# LC_Filter.net
KiCad netlist of a schematic drawn in Altium Designer
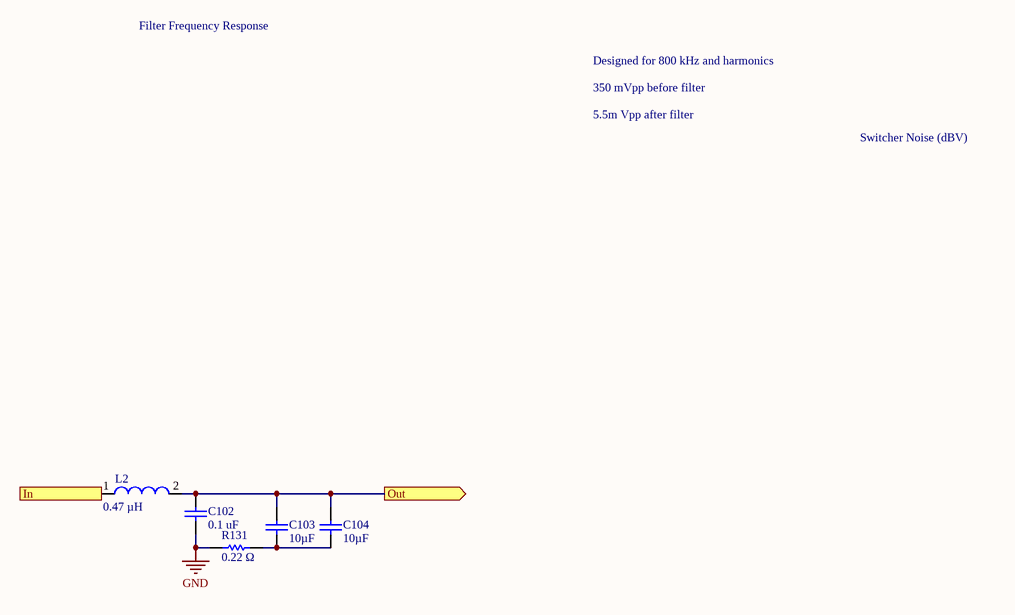
[diagram p0: LC_Filter.SchDoc]

(export (version "E")
  (design (tool "Eeschema 10.0.6"))
  (components
    (comp (ref "C102")
      (value "0.1 uF")
      (footprint "CAPC0402(1005)60_L")
      (description "CAP 100nF 16V ±5% 0402 (1005 Metric) Thickness 0.6mm SMD")
      (fields (field (name "TOLERANCE") "Â±5%"))
      (libsource (lib "Altium Content Vault") (part "CAP"))
    )
    (comp (ref "C103")
      (value "EMK107BBJ106MA-T")
      (footprint "CAPC1608X100X35LL20T25")
      (description "Chip Capacitor, 10 uF, +/- 20%, 16 V, -55 to 85 degC, 0603 (1608 Metric), RoHS, Tape and Reel")
      (fields
        (field (name "CAPACITANCE") "10µF")
        (field (name "MANUFACTURER") "Taiyo Yuden")
        (field (name "TOLERANCE") "±20%")
      )
      (libsource (lib "Altium Content Vault") (part "CAP-NP-2"))
    )
    (comp (ref "C104")
      (value "EMK107BBJ106MA-T")
      (footprint "CAPC1608X100X35LL20T25")
      (description "Chip Capacitor, 10 uF, +/- 20%, 16 V, -55 to 85 degC, 0603 (1608 Metric), RoHS, Tape and Reel")
      (fields
        (field (name "CAPACITANCE") "10µF")
        (field (name "MANUFACTURER") "Taiyo Yuden")
        (field (name "TOLERANCE") "±20%")
      )
      (libsource (lib "Altium Content Vault") (part "CAP-NP-2"))
    )
    (comp (ref "L2")
      (value "74404300047")
      (footprint "WE-TPC-4828-MH")
      (description "SMD Shielded Tiny Power Inductor WE-TPC, L = 0.47 µH")
      (fields (field (name "INDUCTANCE") "0.47 µH"))
      (libsource (lib "Altium Content Vault") (part "PAS-IND-INDUCTOR-2"))
    )
    (comp (ref "R131")
      (value "0.22 Ω")
      (footprint "RESC1608X55X30NL15T15")
      (fields (field (name "PART NUMBER") "ERJ-3RQFR22V") (field (name "MANUFACTURER") "Panasonic"))
      (libsource (lib "Altium Content Vault") (part "RES"))
    )
  )
  (nets
    (net (code "1") (name "/In") (class "Default")
      (node (ref "L2") (pin "1") (pinfunction "1_1") (pintype "passive"))
    )
    (net (code "2") (name "/Out") (class "Default")
      (node (ref "C102") (pin "2") (pinfunction "2_2") (pintype "passive"))
      (node (ref "C103") (pin "2") (pinfunction "2_2") (pintype "passive"))
      (node (ref "C104") (pin "2") (pinfunction "2_2") (pintype "passive"))
      (node (ref "L2") (pin "2") (pinfunction "2_2") (pintype "passive"))
    )
    (net (code "3") (name "GND") (class "Default")
      (node (ref "C102") (pin "1") (pinfunction "1_1") (pintype "passive"))
      (node (ref "R131") (pin "1") (pinfunction "1_1") (pintype "passive"))
    )
    (net (code "4") (name "Net-(C103-Pad1)") (class "Default")
      (node (ref "C103") (pin "1") (pinfunction "1_1") (pintype "passive"))
      (node (ref "C104") (pin "1") (pinfunction "1_1") (pintype "passive"))
      (node (ref "R131") (pin "2") (pinfunction "2_2") (pintype "passive"))
    )
  )
)
